# DigitalSandbox.net
KiCad netlist of a schematic drawn in EAGLE
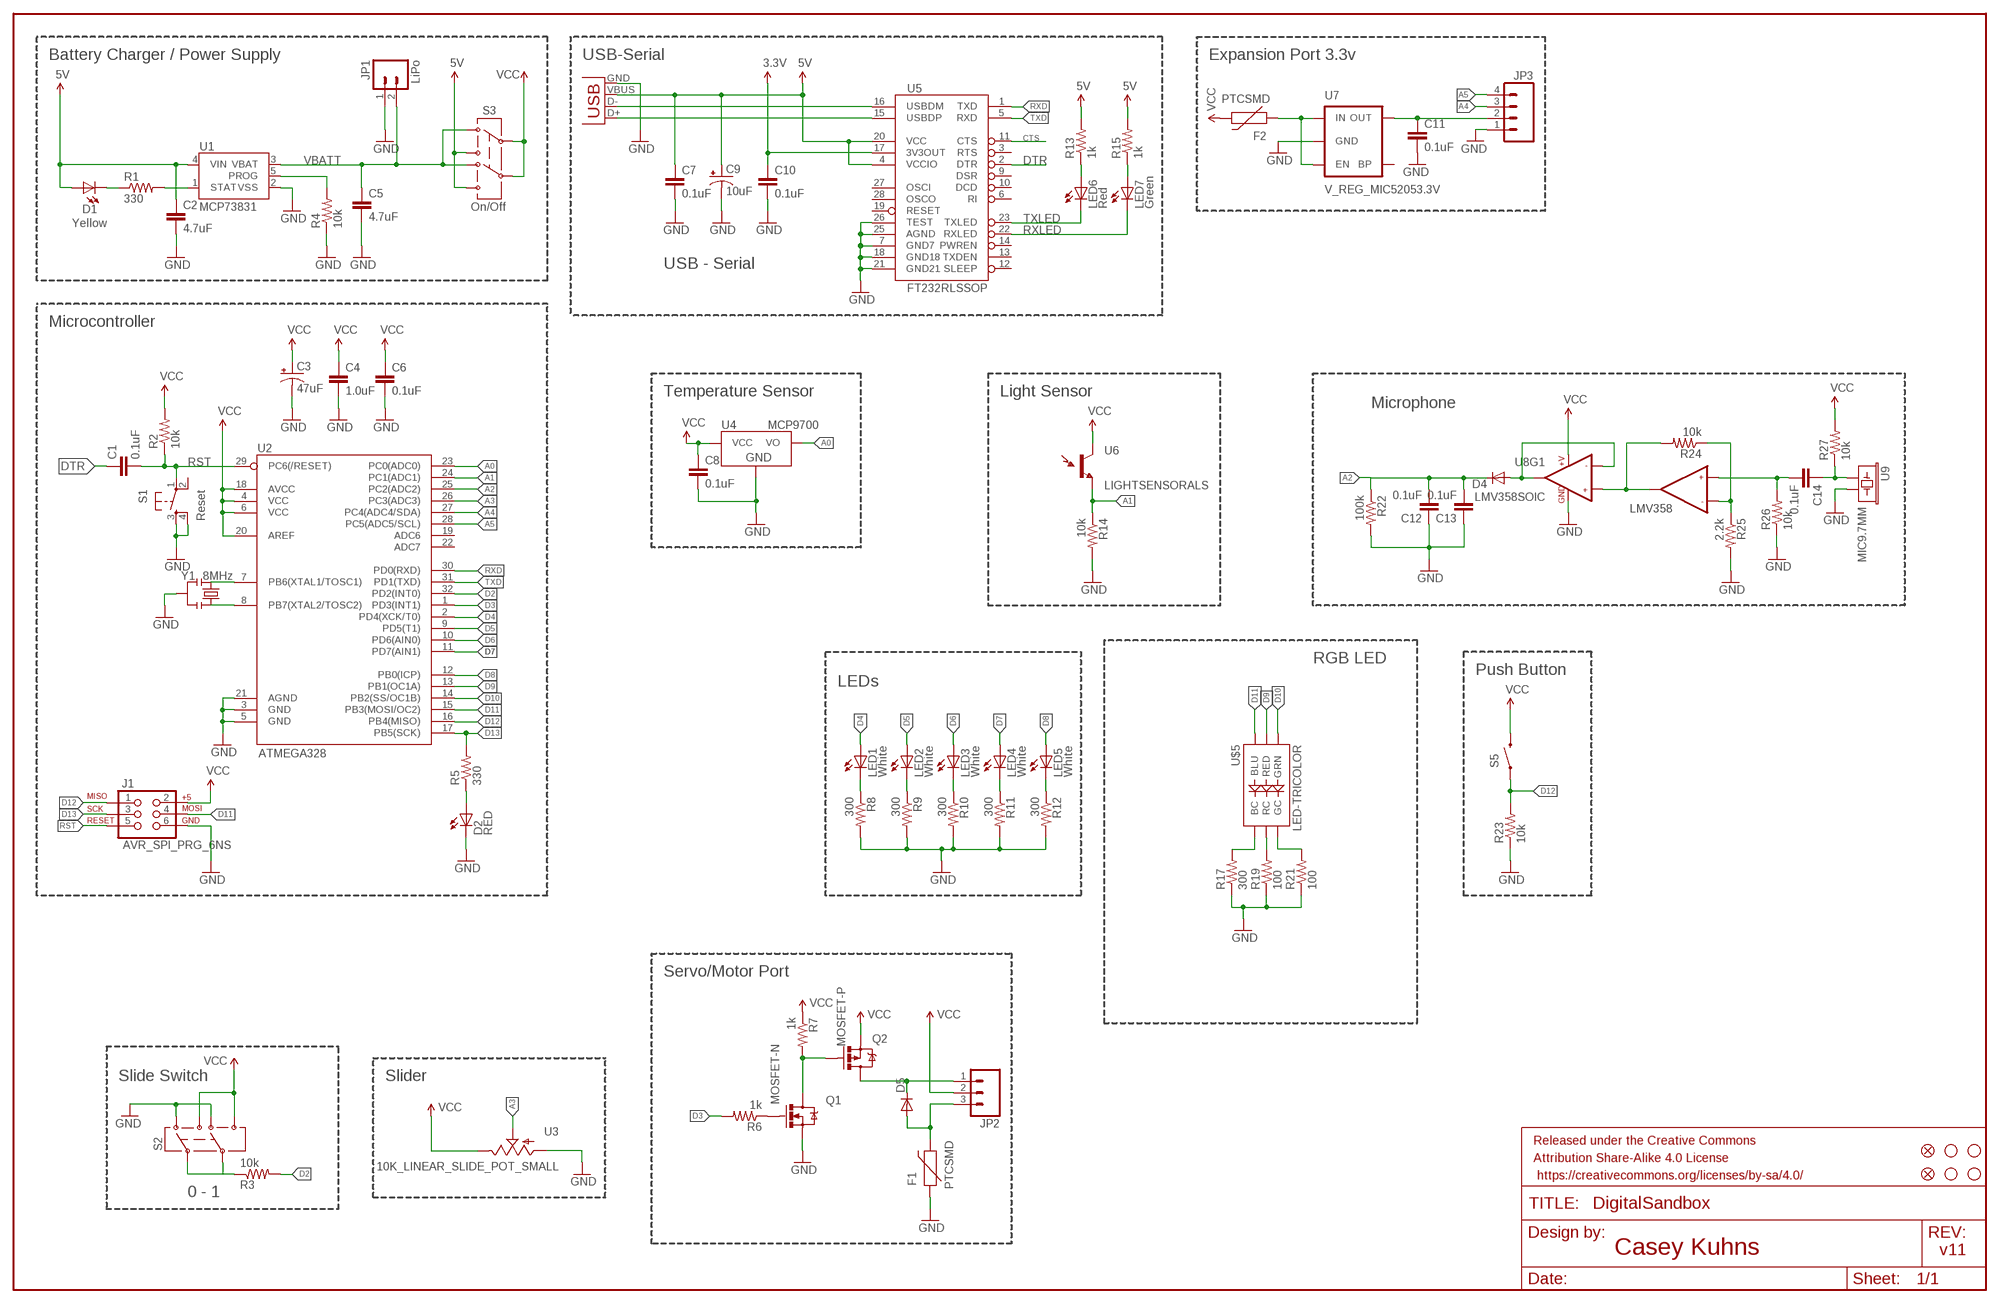
[diagram p0: schematic, sheet 1]

(export (version "E")
  (design (tool "Eeschema 10.0.6"))
  (components
    (comp (ref "C1")
      (value "0.1uF")
      (footprint "eagle-import:0603-CAP")
      (libsource (lib "eagle-import") (part "0.1UF-25V(+80/-20%)(0603)"))
    )
    (comp (ref "C2")
      (value "4.7uF")
      (footprint "eagle-import:0603-CAP")
      (libsource (lib "eagle-import") (part "4.7UF-6.3V-10%(0603)0603"))
    )
    (comp (ref "C3")
      (value "47uF")
      (footprint "eagle-import:EIA3528")
      (libsource (lib "eagle-import") (part "47UF-10V-10%(TANT)"))
    )
    (comp (ref "C4")
      (value "1.0uF")
      (footprint "eagle-import:0603-CAP")
      (libsource (lib "eagle-import") (part "1.0UF-16V-10%(0603)"))
    )
    (comp (ref "C5")
      (value "4.7uF")
      (footprint "eagle-import:0603-CAP")
      (libsource (lib "eagle-import") (part "4.7UF-6.3V-10%(0603)0603"))
    )
    (comp (ref "C6")
      (value "0.1uF")
      (footprint "eagle-import:0603-CAP")
      (libsource (lib "eagle-import") (part "0.1UF-25V(+80/-20%)(0603)"))
    )
    (comp (ref "C7")
      (value "0.1uF")
      (footprint "eagle-import:0603-CAP")
      (libsource (lib "eagle-import") (part "0.1UF-25V(+80/-20%)(0603)"))
    )
    (comp (ref "C8")
      (value "0.1uF")
      (footprint "eagle-import:0603-CAP")
      (libsource (lib "eagle-import") (part "0.1UF-25V(+80/-20%)(0603)"))
    )
    (comp (ref "C9")
      (value "10uF")
      (footprint "eagle-import:EIA3216")
      (libsource (lib "eagle-import") (part "10UF-16V-10%(TANT)"))
    )
    (comp (ref "C10")
      (value "0.1uF")
      (footprint "eagle-import:0603-CAP")
      (libsource (lib "eagle-import") (part "0.1UF-25V(+80/-20%)(0603)"))
    )
    (comp (ref "C11")
      (value "0.1uF")
      (footprint "eagle-import:0603-CAP")
      (libsource (lib "eagle-import") (part "0.1UF-25V(+80/-20%)(0603)"))
    )
    (comp (ref "C12")
      (value "0.1uF")
      (footprint "eagle-import:0603-CAP")
      (libsource (lib "eagle-import") (part "0.1UF-25V(+80/-20%)(0603)"))
    )
    (comp (ref "C13")
      (value "0.1uF")
      (footprint "eagle-import:0603-CAP")
      (libsource (lib "eagle-import") (part "0.1UF-25V(+80/-20%)(0603)"))
    )
    (comp (ref "C14")
      (value "0.1uF")
      (footprint "eagle-import:0603-CAP")
      (libsource (lib "eagle-import") (part "0.1UF-25V(+80/-20%)(0603)"))
    )
    (comp (ref "D1")
      (value "Yellow")
      (footprint "eagle-import:LED-0603")
      (libsource (lib "eagle-import") (part "LED-YELLOW0603"))
    )
    (comp (ref "D2")
      (value "RED")
      (footprint "eagle-import:LED-1206")
      (libsource (lib "eagle-import") (part "LED-RED1206"))
    )
    (comp (ref "D4")
      (value "DIODESOD")
      (footprint "eagle-import:SOD-323")
      (libsource (lib "eagle-import") (part "DIODESOD"))
    )
    (comp (ref "D5")
      (value "DIODESOD")
      (footprint "eagle-import:SOD-323")
      (libsource (lib "eagle-import") (part "DIODESOD"))
    )
    (comp (ref "F1")
      (value "PTCSMD")
      (footprint "eagle-import:PTC-1206")
      (libsource (lib "eagle-import") (part "PTCSMD"))
    )
    (comp (ref "F2")
      (value "PTCSMD")
      (footprint "eagle-import:PTC-1206")
      (libsource (lib "eagle-import") (part "PTCSMD"))
    )
    (comp (ref "FID1")
      (value "FIDUCIAL1X2")
      (footprint "eagle-import:FIDUCIAL-1X2")
      (libsource (lib "eagle-import") (part "FIDUCIAL1X2"))
    )
    (comp (ref "FID2")
      (value "FIDUCIAL1X2")
      (footprint "eagle-import:FIDUCIAL-1X2")
      (libsource (lib "eagle-import") (part "FIDUCIAL1X2"))
    )
    (comp (ref "FRAME1")
      (value "FRAME-LEDGER")
      (footprint "eagle-import:CREATIVE_COMMONS")
      (libsource (lib "eagle-import") (part "FRAME-LEDGER"))
    )
    (comp (ref "J1")
      (value "AVR_SPI_PRG_6NS")
      (footprint "eagle-import:2X3-NS")
      (libsource (lib "eagle-import") (part "AVR_SPI_PRG_6NS"))
    )
    (comp (ref "JP1")
      (value "LiPo")
      (footprint "eagle-import:JST-2-SMD")
      (libsource (lib "eagle-import") (part "M02-JST-2MM-SMT"))
    )
    (comp (ref "JP2")
      (value "M03SMD_RA_FEMALE")
      (footprint "eagle-import:1X03_SMD_RA_FEMALE")
      (libsource (lib "eagle-import") (part "M03SMD_RA_FEMALE"))
    )
    (comp (ref "JP3")
      (value "M04SMD_STRAIGHT_COMBO")
      (footprint "eagle-import:1X04_SMD_STRAIGHT_COMBO")
      (libsource (lib "eagle-import") (part "M04SMD_STRAIGHT_COMBO"))
    )
    (comp (ref "LED1")
      (value "White")
      (footprint "eagle-import:LED-1206")
      (libsource (lib "eagle-import") (part "LED-WHITE"))
    )
    (comp (ref "LED2")
      (value "White")
      (footprint "eagle-import:LED-1206")
      (libsource (lib "eagle-import") (part "LED-WHITE"))
    )
    (comp (ref "LED3")
      (value "White")
      (footprint "eagle-import:LED-1206")
      (libsource (lib "eagle-import") (part "LED-WHITE"))
    )
    (comp (ref "LED4")
      (value "White")
      (footprint "eagle-import:LED-1206")
      (libsource (lib "eagle-import") (part "LED-WHITE"))
    )
    (comp (ref "LED5")
      (value "White")
      (footprint "eagle-import:LED-1206")
      (libsource (lib "eagle-import") (part "LED-WHITE"))
    )
    (comp (ref "LED6")
      (value "Red")
      (footprint "eagle-import:LED-0603")
      (libsource (lib "eagle-import") (part "LED-RED0603"))
    )
    (comp (ref "LED7")
      (value "Green")
      (footprint "eagle-import:LED-0603")
      (libsource (lib "eagle-import") (part "LED-GREEN0603"))
    )
    (comp (ref "Q1")
      (value "MOSFET-N")
      (footprint "eagle-import:SOT23")
      (libsource (lib "eagle-import") (part "MOSFET-NCHANNELBSS138"))
    )
    (comp (ref "Q2")
      (value "MOSFET-P")
      (footprint "eagle-import:SOT23-3")
      (libsource (lib "eagle-import") (part "MOSFET-PCHANNEL"))
    )
    (comp (ref "R1")
      (value "330")
      (footprint "eagle-import:0603-RES")
      (libsource (lib "eagle-import") (part "330OHM1/10W1%(0603)"))
    )
    (comp (ref "R2")
      (value "10k")
      (footprint "eagle-import:0603-RES")
      (libsource (lib "eagle-import") (part "10KOHM1/10W1%(0603)0603"))
    )
    (comp (ref "R3")
      (value "10k")
      (footprint "eagle-import:0603-RES")
      (libsource (lib "eagle-import") (part "10KOHM1/10W1%(0603)0603"))
    )
    (comp (ref "R4")
      (value "10k")
      (footprint "eagle-import:0603-RES")
      (libsource (lib "eagle-import") (part "10KOHM1/10W1%(0603)0603"))
    )
    (comp (ref "R5")
      (value "330")
      (footprint "eagle-import:0603-RES")
      (libsource (lib "eagle-import") (part "330OHM1/10W1%(0603)"))
    )
    (comp (ref "R6")
      (value "1k")
      (footprint "eagle-import:0603-RES")
      (libsource (lib "eagle-import") (part "1KOHM1/10W1%(0603)"))
    )
    (comp (ref "R7")
      (value "1k")
      (footprint "eagle-import:0603-RES")
      (libsource (lib "eagle-import") (part "1KOHM1/10W1%(0603)"))
    )
    (comp (ref "R8")
      (value "300")
      (footprint "eagle-import:0603-RES")
      (libsource (lib "eagle-import") (part "300OHM-1/10W-1%(0603)"))
    )
    (comp (ref "R9")
      (value "300")
      (footprint "eagle-import:0603-RES")
      (libsource (lib "eagle-import") (part "300OHM-1/10W-1%(0603)"))
    )
    (comp (ref "R10")
      (value "300")
      (footprint "eagle-import:0603-RES")
      (libsource (lib "eagle-import") (part "300OHM-1/10W-1%(0603)"))
    )
    (comp (ref "R11")
      (value "300")
      (footprint "eagle-import:0603-RES")
      (libsource (lib "eagle-import") (part "300OHM-1/10W-1%(0603)"))
    )
    (comp (ref "R12")
      (value "300")
      (footprint "eagle-import:0603-RES")
      (libsource (lib "eagle-import") (part "300OHM-1/10W-1%(0603)"))
    )
    (comp (ref "R13")
      (value "1k")
      (footprint "eagle-import:0603-RES")
      (libsource (lib "eagle-import") (part "1KOHM1/10W1%(0603)"))
    )
    (comp (ref "R14")
      (value "10k")
      (footprint "eagle-import:0603-RES")
      (libsource (lib "eagle-import") (part "10KOHM1/10W1%(0603)0603"))
    )
    (comp (ref "R15")
      (value "1k")
      (footprint "eagle-import:0603-RES")
      (libsource (lib "eagle-import") (part "1KOHM1/10W1%(0603)"))
    )
    (comp (ref "R17")
      (value "300")
      (footprint "eagle-import:0603-RES")
      (libsource (lib "eagle-import") (part "300OHM-1/10W-1%(0603)"))
    )
    (comp (ref "R19")
      (value "100")
      (footprint "eagle-import:0603-RES")
      (libsource (lib "eagle-import") (part "100OHM1/10W1%(0603)"))
    )
    (comp (ref "R21")
      (value "100")
      (footprint "eagle-import:0603-RES")
      (libsource (lib "eagle-import") (part "100OHM1/10W1%(0603)"))
    )
    (comp (ref "R22")
      (value "100k")
      (footprint "eagle-import:0603-RES")
      (libsource (lib "eagle-import") (part "100KOHM1/10W1%(0603)"))
    )
    (comp (ref "R23")
      (value "10k")
      (footprint "eagle-import:0603-RES")
      (libsource (lib "eagle-import") (part "10KOHM1/10W1%(0603)0603"))
    )
    (comp (ref "R24")
      (value "10k")
      (footprint "eagle-import:0603-RES")
      (libsource (lib "eagle-import") (part "10KOHM1/10W1%(0603)0603"))
    )
    (comp (ref "R25")
      (value "2.2k")
      (footprint "eagle-import:0603-RES")
      (libsource (lib "eagle-import") (part "2.2KOHM1/10W1%(0603)"))
    )
    (comp (ref "R26")
      (value "10k")
      (footprint "eagle-import:0603-RES")
      (libsource (lib "eagle-import") (part "10KOHM1/10W1%(0603)0603"))
    )
    (comp (ref "R27")
      (value "10k")
      (footprint "eagle-import:0603-RES")
      (libsource (lib "eagle-import") (part "10KOHM1/10W1%(0603)0603"))
    )
    (comp (ref "S1")
      (value "Reset")
      (footprint "eagle-import:TACTILE_SWITCH_SMD")
      (libsource (lib "eagle-import") (part "TAC_SWITCHSMD"))
    )
    (comp (ref "S2")
      (value "SWITCH-DPDTAYZ0202")
      (footprint "eagle-import:AYZ0202")
      (libsource (lib "eagle-import") (part "SWITCH-DPDTAYZ0202"))
    )
    (comp (ref "S3")
      (value "On/Off")
      (footprint "eagle-import:AYZ0202")
      (libsource (lib "eagle-import") (part "SWITCH-DPDTAYZ0202"))
    )
    (comp (ref "S5")
      (value "SWITCH-MOMENTARY-2SMD-4")
      (footprint "eagle-import:TACTILE_SWITCH_TALL")
      (libsource (lib "eagle-import") (part "SWITCH-MOMENTARY-2SMD-4"))
    )
    (comp (ref "STANDOFF1")
      (value "STAND-OFF")
      (footprint "eagle-import:STAND-OFF")
      (libsource (lib "eagle-import") (part "STAND-OFF"))
    )
    (comp (ref "STANDOFF2")
      (value "STAND-OFF")
      (footprint "eagle-import:STAND-OFF")
      (libsource (lib "eagle-import") (part "STAND-OFF"))
    )
    (comp (ref "STANDOFF3")
      (value "STAND-OFF")
      (footprint "eagle-import:STAND-OFF")
      (libsource (lib "eagle-import") (part "STAND-OFF"))
    )
    (comp (ref "STANDOFF4")
      (value "STAND-OFF")
      (footprint "eagle-import:STAND-OFF")
      (libsource (lib "eagle-import") (part "STAND-OFF"))
    )
    (comp (ref "U$5")
      (value "LED-TRICOLOR")
      (footprint "eagle-import:PLCC-6-LED")
      (libsource (lib "eagle-import") (part "LED-TRICOLOR-NO-COMPLCC-6-SMD"))
    )
    (comp (ref "U1")
      (value "MCP73831")
      (footprint "eagle-import:SOT23-5")
      (libsource (lib "eagle-import") (part "MCP73831"))
    )
    (comp (ref "U2")
      (value "ATMEGA328")
      (footprint "eagle-import:TQFP32-08")
      (libsource (lib "eagle-import") (part "ATMEGA328_SMT"))
    )
    (comp (ref "U3")
      (value "10K_LINEAR_SLIDE_POT_SMALL")
      (footprint "eagle-import:C2031N-1A2-B10K-GP")
      (libsource (lib "eagle-import") (part "10K_LINEAR_SLIDE_POT_SMALL"))
    )
    (comp (ref "U4")
      (value "MCP9700")
      (footprint "eagle-import:SOT23-3")
      (libsource (lib "eagle-import") (part "MCP9700SMD"))
    )
    (comp (ref "U5")
      (value "FT232RLSSOP")
      (footprint "eagle-import:SSOP28DB")
      (libsource (lib "eagle-import") (part "FT232RLSSOP"))
    )
    (comp (ref "U6")
      (value "LIGHTSENSORALS")
      (footprint "eagle-import:ALS-PT19")
      (libsource (lib "eagle-import") (part "LIGHTSENSORALS"))
    )
    (comp (ref "U7")
      (value "V_REG_MIC52053.3V")
      (footprint "eagle-import:SOT23-5")
      (libsource (lib "eagle-import") (part "V_REG_MIC52053.3V"))
    )
    (comp (ref "U8")
      (value "LMV358SOIC")
      (footprint "eagle-import:SO08")
      (libsource (lib "eagle-import") (part "LMV358SOIC"))
    )
    (comp (ref "U9")
      (value "MIC9.7MM")
      (footprint "eagle-import:MIC-9.7MM")
      (libsource (lib "eagle-import") (part "MIC9.7MM"))
    )
    (comp (ref "X1")
      (value "USBSMD")
      (footprint "eagle-import:USB-MINIB")
      (libsource (lib "eagle-import") (part "USBSMD"))
    )
    (comp (ref "Y1")
      (value "8MHz")
      (footprint "eagle-import:RESONATOR-SMD")
      (libsource (lib "eagle-import") (part "RESONATOR8MHZ"))
    )
  )
  (nets
    (net (code "1") (name "/CTS") (class "Default")
      (node (ref "U5") (pin "11") (pinfunction "CTS_11") (pintype "input"))
    )
    (net (code "2") (name "/RXLED") (class "Default")
      (node (ref "LED7") (pin "C") (pinfunction "C_C") (pintype "passive"))
      (node (ref "U5") (pin "22") (pinfunction "RXLED_22") (pintype "input"))
    )
    (net (code "3") (name "/TXLED") (class "Default")
      (node (ref "LED6") (pin "C") (pinfunction "C_C") (pintype "passive"))
      (node (ref "U5") (pin "23") (pinfunction "TXLED_23") (pintype "input"))
    )
    (net (code "4") (name "/VBATT") (class "Default")
      (node (ref "C5") (pin "1") (pinfunction "1_1") (pintype "passive"))
      (node (ref "JP1") (pin "2") (pinfunction "1_2") (pintype "passive"))
      (node (ref "S3") (pin "1") (pinfunction "1_1") (pintype "bidirectional"))
      (node (ref "S3") (pin "4") (pinfunction "4_4") (pintype "bidirectional"))
      (node (ref "U1") (pin "3") (pinfunction "VBAT_3") (pintype "power_in"))
    )
    (net (code "5") (name "3.3V") (class "Default")
      (node (ref "C10") (pin "1") (pinfunction "1_1") (pintype "passive"))
      (node (ref "U5") (pin "17") (pinfunction "3V3OUT_17") (pintype "output"))
    )
    (net (code "6") (name "5V") (class "Default")
      (node (ref "C2") (pin "1") (pinfunction "1_1") (pintype "passive"))
      (node (ref "C7") (pin "1") (pinfunction "1_1") (pintype "passive"))
      (node (ref "C9") (pin "A") (pinfunction "+_A") (pintype "passive"))
      (node (ref "D1") (pin "A") (pinfunction "A_A") (pintype "passive"))
      (node (ref "R13") (pin "2") (pinfunction "2_2") (pintype "passive"))
      (node (ref "R15") (pin "2") (pinfunction "2_2") (pintype "passive"))
      (node (ref "S3") (pin "3") (pinfunction "3_3") (pintype "bidirectional"))
      (node (ref "S3") (pin "6") (pinfunction "6_6") (pintype "bidirectional"))
      (node (ref "U1") (pin "4") (pinfunction "VIN_4") (pintype "power_in"))
      (node (ref "U5") (pin "20") (pinfunction "VCC_20") (pintype "power_in"))
      (node (ref "U5") (pin "4") (pinfunction "VCCIO_4") (pintype "power_in"))
      (node (ref "X1") (pin "VBUS") (pinfunction "VBUS_VBUS") (pintype "bidirectional"))
    )
    (net (code "7") (name "A0") (class "Default")
      (node (ref "U2") (pin "23") (pinfunction "PC0(ADC0)_23") (pintype "bidirectional"))
      (node (ref "U4") (pin "2") (pinfunction "VO_2") (pintype "bidirectional"))
    )
    (net (code "8") (name "A1") (class "Default")
      (node (ref "R14") (pin "1") (pinfunction "1_1") (pintype "passive"))
      (node (ref "U2") (pin "24") (pinfunction "PC1(ADC1)_24") (pintype "bidirectional"))
      (node (ref "U6") (pin "E") (pinfunction "E1_E") (pintype "passive"))
    )
    (net (code "9") (name "A2") (class "Default")
      (node (ref "C12") (pin "2") (pinfunction "2_2") (pintype "passive"))
      (node (ref "C13") (pin "2") (pinfunction "2_2") (pintype "passive"))
      (node (ref "D4") (pin "C") (pinfunction "C_C") (pintype "passive"))
      (node (ref "R22") (pin "1") (pinfunction "1_1") (pintype "passive"))
      (node (ref "U2") (pin "25") (pinfunction "PC2(ADC2)_25") (pintype "bidirectional"))
    )
    (net (code "10") (name "A3") (class "Default")
      (node (ref "U2") (pin "26") (pinfunction "PC3(ADC3)_26") (pintype "bidirectional"))
      (node (ref "U3") (pin "1") (pinfunction "S_1") (pintype "passive"))
    )
    (net (code "11") (name "A4") (class "Default")
      (node (ref "JP3") (pin "3") (pinfunction "3_3") (pintype "passive"))
      (node (ref "U2") (pin "27") (pinfunction "PC4(ADC4/SDA)_27") (pintype "bidirectional"))
    )
    (net (code "12") (name "A5") (class "Default")
      (node (ref "JP3") (pin "4") (pinfunction "4_4") (pintype "passive"))
      (node (ref "U2") (pin "28") (pinfunction "PC5(ADC5/SCL)_28") (pintype "bidirectional"))
    )
    (net (code "13") (name "D2") (class "Default")
      (node (ref "R3") (pin "2") (pinfunction "2_2") (pintype "passive"))
      (node (ref "U2") (pin "32") (pinfunction "PD2(INT0)_32") (pintype "bidirectional"))
    )
    (net (code "14") (name "D3") (class "Default")
      (node (ref "R6") (pin "2") (pinfunction "2_2") (pintype "passive"))
      (node (ref "U2") (pin "1") (pinfunction "PD3(INT1)_1") (pintype "bidirectional"))
    )
    (net (code "15") (name "D4") (class "Default")
      (node (ref "LED1") (pin "A") (pinfunction "A_A") (pintype "passive"))
      (node (ref "U2") (pin "2") (pinfunction "PD4(XCK/T0)_2") (pintype "bidirectional"))
    )
    (net (code "16") (name "D5") (class "Default")
      (node (ref "LED2") (pin "A") (pinfunction "A_A") (pintype "passive"))
      (node (ref "U2") (pin "9") (pinfunction "PD5(T1)_9") (pintype "bidirectional"))
    )
    (net (code "17") (name "D6") (class "Default")
      (node (ref "LED3") (pin "A") (pinfunction "A_A") (pintype "passive"))
      (node (ref "U2") (pin "10") (pinfunction "PD6(AIN0)_10") (pintype "bidirectional"))
    )
    (net (code "18") (name "D7") (class "Default")
      (node (ref "LED4") (pin "A") (pinfunction "A_A") (pintype "passive"))
      (node (ref "U2") (pin "11") (pinfunction "PD7(AIN1)_11") (pintype "bidirectional"))
    )
    (net (code "19") (name "D8") (class "Default")
      (node (ref "LED5") (pin "A") (pinfunction "A_A") (pintype "passive"))
      (node (ref "U2") (pin "12") (pinfunction "PB0(ICP)_12") (pintype "bidirectional"))
    )
    (net (code "20") (name "D9") (class "Default")
      (node (ref "U$5") (pin "AR") (pinfunction "RED_AR") (pintype "bidirectional"))
      (node (ref "U2") (pin "13") (pinfunction "PB1(OC1A)_13") (pintype "bidirectional"))
    )
    (net (code "21") (name "D10") (class "Default")
      (node (ref "U$5") (pin "AG") (pinfunction "GRN_AG") (pintype "bidirectional"))
      (node (ref "U2") (pin "14") (pinfunction "PB2(SS/OC1B)_14") (pintype "bidirectional"))
    )
    (net (code "22") (name "D11") (class "Default")
      (node (ref "J1") (pin "4") (pinfunction "4_4") (pintype "passive"))
      (node (ref "U$5") (pin "AB") (pinfunction "BLU_AB") (pintype "bidirectional"))
      (node (ref "U2") (pin "15") (pinfunction "PB3(MOSI/OC2)_15") (pintype "bidirectional"))
    )
    (net (code "23") (name "D12") (class "Default")
      (node (ref "J1") (pin "1") (pinfunction "1_1") (pintype "passive"))
      (node (ref "R23") (pin "2") (pinfunction "2_2") (pintype "passive"))
      (node (ref "S5") (pin "A2") (pinfunction "1_A2") (pintype "passive"))
      (node (ref "U2") (pin "16") (pinfunction "PB4(MISO)_16") (pintype "bidirectional"))
    )
    (net (code "24") (name "D13") (class "Default")
      (node (ref "J1") (pin "3") (pinfunction "3_3") (pintype "passive"))
      (node (ref "R5") (pin "2") (pinfunction "2_2") (pintype "passive"))
      (node (ref "U2") (pin "17") (pinfunction "PB5(SCK)_17") (pintype "bidirectional"))
    )
    (net (code "25") (name "DTR") (class "Default")
      (node (ref "C1") (pin "1") (pinfunction "1_1") (pintype "passive"))
      (node (ref "U5") (pin "2") (pinfunction "DTR_2") (pintype "output"))
    )
    (net (code "26") (name "GND") (class "Default")
      (node (ref "C10") (pin "2") (pinfunction "2_2") (pintype "passive"))
      (node (ref "C11") (pin "2") (pinfunction "2_2") (pintype "passive"))
      (node (ref "C12") (pin "1") (pinfunction "1_1") (pintype "passive"))
      (node (ref "C13") (pin "1") (pinfunction "1_1") (pintype "passive"))
      (node (ref "C2") (pin "2") (pinfunction "2_2") (pintype "passive"))
      (node (ref "C3") (pin "C") (pinfunction "-_C") (pintype "passive"))
      (node (ref "C4") (pin "2") (pinfunction "2_2") (pintype "passive"))
      (node (ref "C5") (pin "2") (pinfunction "2_2") (pintype "passive"))
      (node (ref "C6") (pin "2") (pinfunction "2_2") (pintype "passive"))
      (node (ref "C7") (pin "2") (pinfunction "2_2") (pintype "passive"))
      (node (ref "C8") (pin "2") (pinfunction "2_2") (pintype "passive"))
      (node (ref "C9") (pin "C") (pinfunction "-_C") (pintype "passive"))
      (node (ref "D2") (pin "C") (pinfunction "C_C") (pintype "passive"))
      (node (ref "F1") (pin "1") (pinfunction "1_1") (pintype "bidirectional"))
      (node (ref "J1") (pin "6") (pinfunction "6_6") (pintype "passive"))
      (node (ref "JP1") (pin "1") (pinfunction "2_1") (pintype "passive"))
      (node (ref "JP3") (pin "1") (pinfunction "1_1") (pintype "passive"))
      (node (ref "Q1") (pin "2") (pinfunction "S_2") (pintype "passive"))
      (node (ref "R10") (pin "2") (pinfunction "2_2") (pintype "passive"))
      (node (ref "R11") (pin "2") (pinfunction "2_2") (pintype "passive"))
      (node (ref "R12") (pin "2") (pinfunction "2_2") (pintype "passive"))
      (node (ref "R14") (pin "2") (pinfunction "2_2") (pintype "passive"))
      (node (ref "R17") (pin "1") (pinfunction "1_1") (pintype "passive"))
      (node (ref "R19") (pin "1") (pinfunction "1_1") (pintype "passive"))
      (node (ref "R21") (pin "1") (pinfunction "1_1") (pintype "passive"))
      (node (ref "R22") (pin "2") (pinfunction "2_2") (pintype "passive"))
      (node (ref "R23") (pin "1") (pinfunction "1_1") (pintype "passive"))
      (node (ref "R25") (pin "2") (pinfunction "2_2") (pintype "passive"))
      (node (ref "R26") (pin "1") (pinfunction "1_1") (pintype "passive"))
      (node (ref "R4") (pin "1") (pinfunction "1_1") (pintype "passive"))
      (node (ref "R8") (pin "2") (pinfunction "2_2") (pintype "passive"))
      (node (ref "R9") (pin "2") (pinfunction "2_2") (pintype "passive"))
      (node (ref "S1") (pin "3") (pinfunction "3_3") (pintype "passive"))
      (node (ref "S1") (pin "4") (pinfunction "4_4") (pintype "passive"))
      (node (ref "S2") (pin "1") (pinfunction "1_1") (pintype "bidirectional"))
      (node (ref "S2") (pin "4") (pinfunction "4_4") (pintype "bidirectional"))
      (node (ref "U1") (pin "2") (pinfunction "VSS_2") (pintype "power_in"))
      (node (ref "U2") (pin "21") (pinfunction "AGND_21") (pintype "bidirectional"))
      (node (ref "U2") (pin "3") (pinfunction "GND_3") (pintype "bidirectional"))
      (node (ref "U2") (pin "5") (pinfunction "GND_5") (pintype "bidirectional"))
      (node (ref "U3") (pin "2") (pinfunction "A_2") (pintype "passive"))
      (node (ref "U4") (pin "3") (pinfunction "GND_3") (pintype "bidirectional"))
      (node (ref "U5") (pin "18") (pinfunction "GND18_18") (pintype "power_in"))
      (node (ref "U5") (pin "21") (pinfunction "GND21_21") (pintype "power_in"))
      (node (ref "U5") (pin "25") (pinfunction "AGND_25") (pintype "power_in"))
      (node (ref "U5") (pin "26") (pinfunction "TEST_26") (pintype "input"))
      (node (ref "U5") (pin "7") (pinfunction "GND7_7") (pintype "power_in"))
      (node (ref "U7") (pin "2") (pinfunction "GND_2") (pintype "input"))
      (node (ref "U8") (pin "4") (pinfunction "GND_4") (pintype "power_in"))
      (node (ref "U9") (pin "2") (pinfunction "2_2") (pintype "passive"))
      (node (ref "X1") (pin "GND") (pinfunction "GND_GND") (pintype "bidirectional"))
      (node (ref "Y1") (pin "2") (pinfunction "2_2") (pintype "passive"))
    )
    (net (code "27") (name "Net-(C14-Pad1)") (class "Default")
      (node (ref "C14") (pin "1") (pinfunction "1_1") (pintype "passive"))
      (node (ref "R27") (pin "1") (pinfunction "1_1") (pintype "passive"))
      (node (ref "U9") (pin "1") (pinfunction "1_1") (pintype "passive"))
    )
    (net (code "28") (name "Net-(D1-PadC)") (class "Default")
      (node (ref "D1") (pin "C") (pinfunction "C_C") (pintype "passive"))
      (node (ref "R1") (pin "1") (pinfunction "1_1") (pintype "passive"))
    )
    (net (code "29") (name "Net-(D2-PadA)") (class "Default")
      (node (ref "D2") (pin "A") (pinfunction "A_A") (pintype "passive"))
      (node (ref "R5") (pin "1") (pinfunction "1_1") (pintype "passive"))
    )
    (net (code "30") (name "Net-(D5-PadA)") (class "Default")
      (node (ref "D5") (pin "A") (pinfunction "A_A") (pintype "passive"))
      (node (ref "F1") (pin "2") (pinfunction "2_2") (pintype "bidirectional"))
      (node (ref "JP2") (pin "3") (pinfunction "3_3") (pintype "passive"))
    )
    (net (code "31") (name "Net-(LED1-PadC)") (class "Default")
      (node (ref "LED1") (pin "C") (pinfunction "C_C") (pintype "passive"))
      (node (ref "R8") (pin "1") (pinfunction "1_1") (pintype "passive"))
    )
    (net (code "32") (name "Net-(LED2-PadC)") (class "Default")
      (node (ref "LED2") (pin "C") (pinfunction "C_C") (pintype "passive"))
      (node (ref "R9") (pin "1") (pinfunction "1_1") (pintype "passive"))
    )
    (net (code "33") (name "Net-(LED3-PadC)") (class "Default")
      (node (ref "LED3") (pin "C") (pinfunction "C_C") (pintype "passive"))
      (node (ref "R10") (pin "1") (pinfunction "1_1") (pintype "passive"))
    )
    (net (code "34") (name "Net-(LED4-PadC)") (class "Default")
      (node (ref "LED4") (pin "C") (pinfunction "C_C") (pintype "passive"))
      (node (ref "R11") (pin "1") (pinfunction "1_1") (pintype "passive"))
    )
    (net (code "35") (name "Net-(LED5-PadC)") (class "Default")
      (node (ref "LED5") (pin "C") (pinfunction "C_C") (pintype "passive"))
      (node (ref "R12") (pin "1") (pinfunction "1_1") (pintype "passive"))
    )
    (net (code "36") (name "Net-(LED6-PadA)") (class "Default")
      (node (ref "LED6") (pin "A") (pinfunction "A_A") (pintype "passive"))
      (node (ref "R13") (pin "1") (pinfunction "1_1") (pintype "passive"))
    )
    (net (code "37") (name "Net-(LED7-PadA)") (class "Default")
      (node (ref "LED7") (pin "A") (pinfunction "A_A") (pintype "passive"))
      (node (ref "R15") (pin "1") (pinfunction "1_1") (pintype "passive"))
    )
    (net (code "38") (name "Net-(Q1-D)") (class "Default")
      (node (ref "Q1") (pin "3") (pinfunction "D_3") (pintype "passive"))
      (node (ref "Q2") (pin "1") (pinfunction "G_1") (pintype "passive"))
      (node (ref "R7") (pin "2") (pinfunction "2_2") (pintype "passive"))
    )
    (net (code "39") (name "Net-(Q1-G)") (class "Default")
      (node (ref "Q1") (pin "1") (pinfunction "G_1") (pintype "passive"))
      (node (ref "R6") (pin "1") (pinfunction "1_1") (pintype "passive"))
    )
    (net (code "40") (name "Net-(Q2-D)") (class "Default")
      (node (ref "D5") (pin "C") (pinfunction "C_C") (pintype "passive"))
      (node (ref "JP2") (pin "1") (pinfunction "1_1") (pintype "passive"))
      (node (ref "Q2") (pin "3") (pinfunction "D_3") (pintype "passive"))
    )
    (net (code "41") (name "Net-(R3-Pad1)") (class "Default")
      (node (ref "R3") (pin "1") (pinfunction "1_1") (pintype "passive"))
      (node (ref "S2") (pin "2") (pinfunction "2_2") (pintype "bidirectional"))
      (node (ref "S2") (pin "5") (pinfunction "5_5") (pintype "bidirectional"))
    )
    (net (code "42") (name "Net-(U$5-BC)") (class "Default")
      (node (ref "R17") (pin "2") (pinfunction "2_2") (pintype "passive"))
      (node (ref "U$5") (pin "CB") (pinfunction "BC_CB") (pintype "bidirectional"))
    )
    (net (code "43") (name "Net-(U$5-GC)") (class "Default")
      (node (ref "R21") (pin "2") (pinfunction "2_2") (pintype "passive"))
      (node (ref "U$5") (pin "CG") (pinfunction "GC_CG") (pintype "bidirectional"))
    )
    (net (code "44") (name "Net-(U$5-RC)") (class "Default")
      (node (ref "R19") (pin "2") (pinfunction "2_2") (pintype "passive"))
      (node (ref "U$5") (pin "CR") (pinfunction "RC_CR") (pintype "bidirectional"))
    )
    (net (code "45") (name "Net-(U1-PROG)") (class "Default")
      (node (ref "R4") (pin "2") (pinfunction "2_2") (pintype "passive"))
      (node (ref "U1") (pin "5") (pinfunction "PROG_5") (pintype "input"))
    )
    (net (code "46") (name "Net-(U1-STAT)") (class "Default")
      (node (ref "R1") (pin "2") (pinfunction "2_2") (pintype "passive"))
      (node (ref "U1") (pin "1") (pinfunction "STAT_1") (pintype "output"))
    )
    (net (code "47") (name "Net-(U2-PB6(XTAL1{slash}TOSC1))") (class "Default")
      (node (ref "U2") (pin "7") (pinfunction "PB6(XTAL1/TOSC1)_7") (pintype "bidirectional"))
      (node (ref "Y1") (pin "1") (pinfunction "1_1") (pintype "passive"))
    )
    (net (code "48") (name "Net-(U2-PB7(XTAL2{slash}TOSC2))") (class "Default")
      (node (ref "U2") (pin "8") (pinfunction "PB7(XTAL2/TOSC2)_8") (pintype "bidirectional"))
      (node (ref "Y1") (pin "3") (pinfunction "3_3") (pintype "passive"))
    )
    (net (code "49") (name "Net-(U5-USBDM)") (class "Default")
      (node (ref "U5") (pin "16") (pinfunction "USBDM_16") (pintype "bidirectional"))
      (node (ref "X1") (pin "D-") (pinfunction "D-_D-") (pintype "bidirectional"))
    )
    (net (code "50") (name "Net-(U5-USBDP)") (class "Default")
      (node (ref "U5") (pin "15") (pinfunction "USBDP_15") (pintype "bidirectional"))
      (node (ref "X1") (pin "D+") (pinfunction "D+_D+") (pintype "bidirectional"))
    )
    (net (code "51") (name "Net-(U7-EN)") (class "Default")
      (node (ref "F2") (pin "1") (pinfunction "1_1") (pintype "bidirectional"))
      (node (ref "U7") (pin "1") (pinfunction "IN_1") (pintype "input"))
      (node (ref "U7") (pin "3") (pinfunction "EN_3") (pintype "input"))
    )
    (net (code "52") (name "Net-(U7-OUT)") (class "Default")
      (node (ref "C11") (pin "1") (pinfunction "1_1") (pintype "passive"))
      (node (ref "JP3") (pin "2") (pinfunction "2_2") (pintype "passive"))
      (node (ref "U7") (pin "5") (pinfunction "OUT_5") (pintype "passive"))
    )
    (net (code "53") (name "Net-(U8A-+IN1)") (class "Default")
      (node (ref "R24") (pin "2") (pinfunction "2_2") (pintype "passive"))
      (node (ref "U8") (pin "3") (pinfunction "+IN1_3") (pintype "input"))
      (node (ref "U8") (pin "7") (pinfunction "OUT2_7") (pintype "output"))
    )
    (net (code "54") (name "Net-(U8A--IN1)") (class "Default")
      (node (ref "D4") (pin "A") (pinfunction "A_A") (pintype "passive"))
      (node (ref "U8") (pin "1") (pinfunction "OUT1_1") (pintype "output"))
      (node (ref "U8") (pin "2") (pinfunction "-IN1_2") (pintype "input"))
    )
    (net (code "55") (name "Net-(U8B-+IN2)") (class "Default")
      (node (ref "C14") (pin "2") (pinfunction "2_2") (pintype "passive"))
      (node (ref "R26") (pin "2") (pinfunction "2_2") (pintype "passive"))
      (node (ref "U8") (pin "5") (pinfunction "+IN2_5") (pintype "input"))
    )
    (net (code "56") (name "Net-(U8B--IN2)") (class "Default")
      (node (ref "R24") (pin "1") (pinfunction "1_1") (pintype "passive"))
      (node (ref "R25") (pin "1") (pinfunction "1_1") (pintype "passive"))
      (node (ref "U8") (pin "6") (pinfunction "-IN2_6") (pintype "input"))
    )
    (net (code "57") (name "RST") (class "Default")
      (node (ref "C1") (pin "2") (pinfunction "2_2") (pintype "passive"))
      (node (ref "J1") (pin "5") (pinfunction "5_5") (pintype "passive"))
      (node (ref "R2") (pin "1") (pinfunction "1_1") (pintype "passive"))
      (node (ref "S1") (pin "1") (pinfunction "1_1") (pintype "passive"))
      (node (ref "U2") (pin "29") (pinfunction "PC6(/RESET)_29") (pintype "bidirectional"))
    )
    (net (code "58") (name "RXD") (class "Default")
      (node (ref "U2") (pin "30") (pinfunction "PD0(RXD)_30") (pintype "bidirectional"))
      (node (ref "U5") (pin "1") (pinfunction "TXD_1") (pintype "output"))
    )
    (net (code "59") (name "TXD") (class "Default")
      (node (ref "U2") (pin "31") (pinfunction "PD1(TXD)_31") (pintype "bidirectional"))
      (node (ref "U5") (pin "5") (pinfunction "RXD_5") (pintype "input"))
    )
    (net (code "60") (name "VCC") (class "Default")
      (node (ref "C3") (pin "A") (pinfunction "+_A") (pintype "passive"))
      (node (ref "C4") (pin "1") (pinfunction "1_1") (pintype "passive"))
      (node (ref "C6") (pin "1") (pinfunction "1_1") (pintype "passive"))
      (node (ref "C8") (pin "1") (pinfunction "1_1") (pintype "passive"))
      (node (ref "F2") (pin "2") (pinfunction "2_2") (pintype "bidirectional"))
      (node (ref "J1") (pin "2") (pinfunction "2_2") (pintype "passive"))
      (node (ref "JP2") (pin "2") (pinfunction "2_2") (pintype "passive"))
      (node (ref "Q2") (pin "2") (pinfunction "S_2") (pintype "passive"))
      (node (ref "R2") (pin "2") (pinfunction "2_2") (pintype "passive"))
      (node (ref "R27") (pin "2") (pinfunction "2_2") (pintype "passive"))
      (node (ref "R7") (pin "1") (pinfunction "1_1") (pintype "passive"))
      (node (ref "S2") (pin "3") (pinfunction "3_3") (pintype "bidirectional"))
      (node (ref "S2") (pin "6") (pinfunction "6_6") (pintype "bidirectional"))
      (node (ref "S3") (pin "2") (pinfunction "2_2") (pintype "bidirectional"))
      (node (ref "S3") (pin "5") (pinfunction "5_5") (pintype "bidirectional"))
      (node (ref "S5") (pin "B2") (pinfunction "2_B2") (pintype "passive"))
      (node (ref "U2") (pin "18") (pinfunction "AVCC_18") (pintype "bidirectional"))
      (node (ref "U2") (pin "20") (pinfunction "AREF_20") (pintype "bidirectional"))
      (node (ref "U2") (pin "4") (pinfunction "VCC_4") (pintype "bidirectional"))
      (node (ref "U2") (pin "6") (pinfunction "VCC_6") (pintype "bidirectional"))
      (node (ref "U3") (pin "3") (pinfunction "E_3") (pintype "passive"))
      (node (ref "U4") (pin "1") (pinfunction "VCC_1") (pintype "bidirectional"))
      (node (ref "U6") (pin "C") (pinfunction "C1_C") (pintype "passive"))
      (node (ref "U8") (pin "8") (pinfunction "+V_8") (pintype "power_in"))
    )
    (net (code "61") (name "unconnected-(S1-Pad2)") (class "Default")
      (node (ref "S1") (pin "2") (pinfunction "2_2") (pintype "passive"))
    )
    (net (code "62") (name "unconnected-(U2-ADC6-Pad19)") (class "Default")
      (node (ref "U2") (pin "19") (pinfunction "ADC6_19") (pintype "bidirectional"))
    )
    (net (code "63") (name "unconnected-(U2-ADC7-Pad22)") (class "Default")
      (node (ref "U2") (pin "22") (pinfunction "ADC7_22") (pintype "bidirectional"))
    )
    (net (code "64") (name "unconnected-(U5-DCD-Pad10)") (class "Default")
      (node (ref "U5") (pin "10") (pinfunction "DCD_10") (pintype "input"))
    )
    (net (code "65") (name "unconnected-(U5-DSR-Pad9)") (class "Default")
      (node (ref "U5") (pin "9") (pinfunction "DSR_9") (pintype "input"))
    )
    (net (code "66") (name "unconnected-(U5-OSCI-Pad27)") (class "Default")
      (node (ref "U5") (pin "27") (pinfunction "OSCI_27") (pintype "input"))
    )
    (net (code "67") (name "unconnected-(U5-OSCO-Pad28)") (class "Default")
      (node (ref "U5") (pin "28") (pinfunction "OSCO_28") (pintype "output"))
    )
    (net (code "68") (name "unconnected-(U5-PWREN-Pad14)") (class "Default")
      (node (ref "U5") (pin "14") (pinfunction "PWREN_14") (pintype "input"))
    )
    (net (code "69") (name "unconnected-(U5-RESET-Pad19)") (class "Default")
      (node (ref "U5") (pin "19") (pinfunction "RESET_19") (pintype "input"))
    )
    (net (code "70") (name "unconnected-(U5-RI-Pad6)") (class "Default")
      (node (ref "U5") (pin "6") (pinfunction "RI_6") (pintype "input"))
    )
    (net (code "71") (name "unconnected-(U5-RTS-Pad3)") (class "Default")
      (node (ref "U5") (pin "3") (pinfunction "RTS_3") (pintype "output"))
    )
    (net (code "72") (name "unconnected-(U5-SLEEP-Pad12)") (class "Default")
      (node (ref "U5") (pin "12") (pinfunction "SLEEP_12") (pintype "input"))
    )
    (net (code "73") (name "unconnected-(U5-TXDEN-Pad13)") (class "Default")
      (node (ref "U5") (pin "13") (pinfunction "TXDEN_13") (pintype "input"))
    )
    (net (code "74") (name "unconnected-(U7-BP-Pad4)") (class "Default")
      (node (ref "U7") (pin "4") (pinfunction "BP_4") (pintype "input"))
    )
  )
)
